# memory.net
KiCad netlist of a schematic drawn in Altium Designer
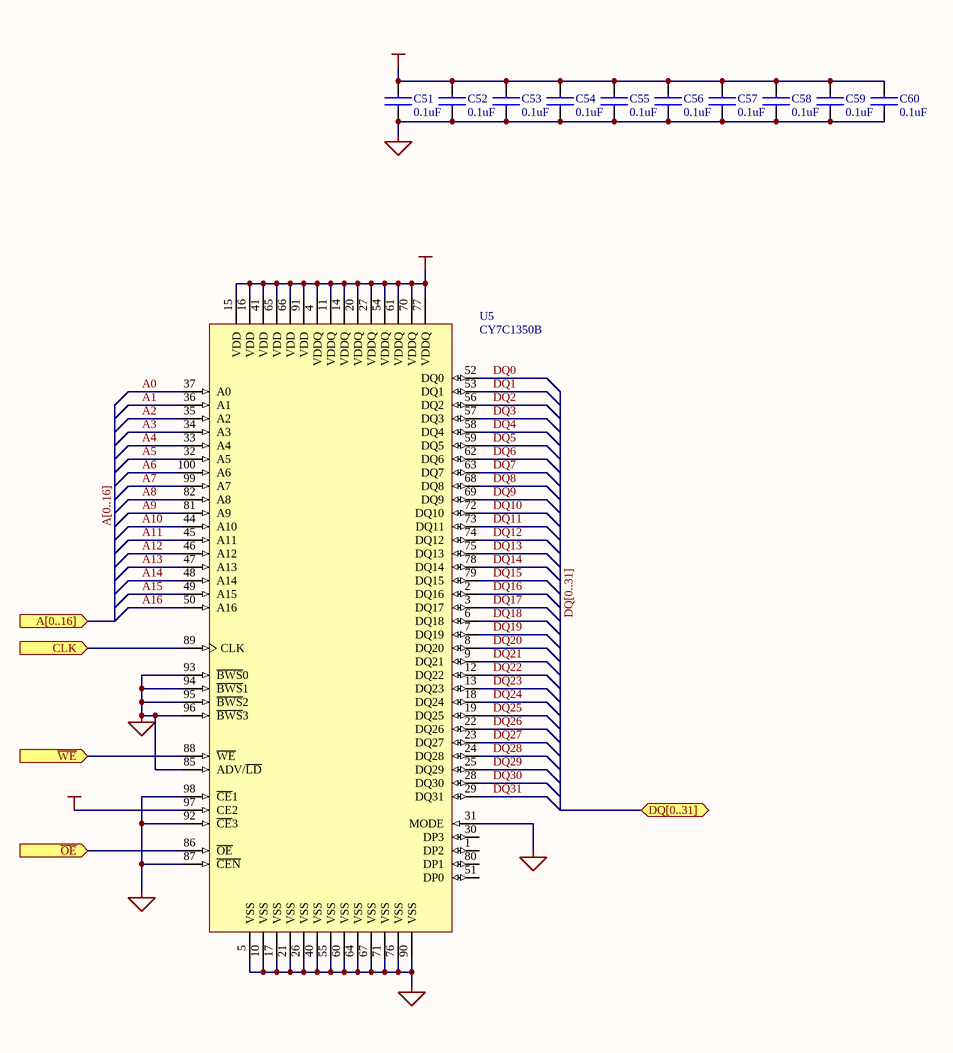
[diagram p0: memory.SCHDOC]

(export (version "E")
  (design (tool "Eeschema 10.0.6"))
  (components
    (comp (ref "C51")
      (value "0.1uF")
      (footprint "0603")
      (description "Standard Capacitor")
      (fields (field (name "Comment") "CAPACITOR"))
      (libsource (lib "parts") (part "CAPACITOR"))
    )
    (comp (ref "C52")
      (value "0.1uF")
      (footprint "0603")
      (description "Standard Capacitor")
      (fields (field (name "Comment") "CAPACITOR"))
      (libsource (lib "parts") (part "CAPACITOR"))
    )
    (comp (ref "C53")
      (value "0.1uF")
      (footprint "0603")
      (description "Standard Capacitor")
      (fields (field (name "Comment") "CAPACITOR"))
      (libsource (lib "parts") (part "CAPACITOR"))
    )
    (comp (ref "C54")
      (value "0.1uF")
      (footprint "0603")
      (description "Standard Capacitor")
      (fields (field (name "Comment") "CAPACITOR"))
      (libsource (lib "parts") (part "CAPACITOR"))
    )
    (comp (ref "C55")
      (value "0.1uF")
      (footprint "0603")
      (description "Standard Capacitor")
      (fields (field (name "Comment") "CAPACITOR"))
      (libsource (lib "parts") (part "CAPACITOR"))
    )
    (comp (ref "C56")
      (value "0.1uF")
      (footprint "0603")
      (description "Standard Capacitor")
      (fields (field (name "Comment") "CAPACITOR"))
      (libsource (lib "parts") (part "CAPACITOR"))
    )
    (comp (ref "C57")
      (value "0.1uF")
      (footprint "0603")
      (description "Standard Capacitor")
      (fields (field (name "Comment") "CAPACITOR"))
      (libsource (lib "parts") (part "CAPACITOR"))
    )
    (comp (ref "C58")
      (value "0.1uF")
      (footprint "0603")
      (description "Standard Capacitor")
      (fields (field (name "Comment") "CAPACITOR"))
      (libsource (lib "parts") (part "CAPACITOR"))
    )
    (comp (ref "C59")
      (value "0.1uF")
      (footprint "0603")
      (description "Standard Capacitor")
      (fields (field (name "Comment") "CAPACITOR"))
      (libsource (lib "parts") (part "CAPACITOR"))
    )
    (comp (ref "C60")
      (value "0.1uF")
      (footprint "0603")
      (description "Standard Capacitor")
      (fields (field (name "Comment") "CAPACITOR"))
      (libsource (lib "parts") (part "CAPACITOR"))
    )
    (comp (ref "U5")
      (value "CY7C1350B")
      (footprint "R-QFP14x20-G100/N")
      (description "Cypress NoBL Pipelined SRAM 128kx36")
      (libsource (lib "My devices") (part "CY7C1350B"))
    )
  )
  (nets
    (net (code "1") (name "/A0") (class "Default")
      (node (ref "U5") (pin "37") (pinfunction "A0_37") (pintype "input"))
    )
    (net (code "2") (name "/A1") (class "Default")
      (node (ref "U5") (pin "36") (pinfunction "A1_36") (pintype "input"))
    )
    (net (code "3") (name "/A2") (class "Default")
      (node (ref "U5") (pin "35") (pinfunction "A2_35") (pintype "input"))
    )
    (net (code "4") (name "/A3") (class "Default")
      (node (ref "U5") (pin "34") (pinfunction "A3_34") (pintype "input"))
    )
    (net (code "5") (name "/A4") (class "Default")
      (node (ref "U5") (pin "33") (pinfunction "A4_33") (pintype "input"))
    )
    (net (code "6") (name "/A5") (class "Default")
      (node (ref "U5") (pin "32") (pinfunction "A5_32") (pintype "input"))
    )
    (net (code "7") (name "/A6") (class "Default")
      (node (ref "U5") (pin "100") (pinfunction "A6_100") (pintype "input"))
    )
    (net (code "8") (name "/A7") (class "Default")
      (node (ref "U5") (pin "99") (pinfunction "A7_99") (pintype "input"))
    )
    (net (code "9") (name "/A8") (class "Default")
      (node (ref "U5") (pin "82") (pinfunction "A8_82") (pintype "input"))
    )
    (net (code "10") (name "/A9") (class "Default")
      (node (ref "U5") (pin "81") (pinfunction "A9_81") (pintype "input"))
    )
    (net (code "11") (name "/A10") (class "Default")
      (node (ref "U5") (pin "44") (pinfunction "A10_44") (pintype "input"))
    )
    (net (code "12") (name "/A11") (class "Default")
      (node (ref "U5") (pin "45") (pinfunction "A11_45") (pintype "input"))
    )
    (net (code "13") (name "/A12") (class "Default")
      (node (ref "U5") (pin "46") (pinfunction "A12_46") (pintype "input"))
    )
    (net (code "14") (name "/A13") (class "Default")
      (node (ref "U5") (pin "47") (pinfunction "A13_47") (pintype "input"))
    )
    (net (code "15") (name "/A14") (class "Default")
      (node (ref "U5") (pin "48") (pinfunction "A14_48") (pintype "input"))
    )
    (net (code "16") (name "/A15") (class "Default")
      (node (ref "U5") (pin "49") (pinfunction "A15_49") (pintype "input"))
    )
    (net (code "17") (name "/A16") (class "Default")
      (node (ref "U5") (pin "50") (pinfunction "A16_50") (pintype "input"))
    )
    (net (code "19") (name "/CLK") (class "Default")
      (node (ref "U5") (pin "89") (pinfunction "CLK_89") (pintype "input"))
    )
    (net (code "20") (name "/DQ0") (class "Default")
      (node (ref "U5") (pin "52") (pinfunction "DQ0_52") (pintype "bidirectional"))
    )
    (net (code "21") (name "/DQ1") (class "Default")
      (node (ref "U5") (pin "53") (pinfunction "DQ1_53") (pintype "bidirectional"))
    )
    (net (code "22") (name "/DQ2") (class "Default")
      (node (ref "U5") (pin "56") (pinfunction "DQ2_56") (pintype "bidirectional"))
    )
    (net (code "23") (name "/DQ3") (class "Default")
      (node (ref "U5") (pin "57") (pinfunction "DQ3_57") (pintype "bidirectional"))
    )
    (net (code "24") (name "/DQ4") (class "Default")
      (node (ref "U5") (pin "58") (pinfunction "DQ4_58") (pintype "bidirectional"))
    )
    (net (code "25") (name "/DQ5") (class "Default")
      (node (ref "U5") (pin "59") (pinfunction "DQ5_59") (pintype "bidirectional"))
    )
    (net (code "26") (name "/DQ6") (class "Default")
      (node (ref "U5") (pin "62") (pinfunction "DQ6_62") (pintype "bidirectional"))
    )
    (net (code "27") (name "/DQ7") (class "Default")
      (node (ref "U5") (pin "63") (pinfunction "DQ7_63") (pintype "bidirectional"))
    )
    (net (code "28") (name "/DQ8") (class "Default")
      (node (ref "U5") (pin "68") (pinfunction "DQ8_68") (pintype "bidirectional"))
    )
    (net (code "29") (name "/DQ9") (class "Default")
      (node (ref "U5") (pin "69") (pinfunction "DQ9_69") (pintype "bidirectional"))
    )
    (net (code "30") (name "/DQ10") (class "Default")
      (node (ref "U5") (pin "72") (pinfunction "DQ10_72") (pintype "bidirectional"))
    )
    (net (code "31") (name "/DQ11") (class "Default")
      (node (ref "U5") (pin "73") (pinfunction "DQ11_73") (pintype "bidirectional"))
    )
    (net (code "32") (name "/DQ12") (class "Default")
      (node (ref "U5") (pin "74") (pinfunction "DQ12_74") (pintype "bidirectional"))
    )
    (net (code "33") (name "/DQ13") (class "Default")
      (node (ref "U5") (pin "75") (pinfunction "DQ13_75") (pintype "bidirectional"))
    )
    (net (code "34") (name "/DQ14") (class "Default")
      (node (ref "U5") (pin "78") (pinfunction "DQ14_78") (pintype "bidirectional"))
    )
    (net (code "35") (name "/DQ15") (class "Default")
      (node (ref "U5") (pin "79") (pinfunction "DQ15_79") (pintype "bidirectional"))
    )
    (net (code "36") (name "/DQ16") (class "Default")
      (node (ref "U5") (pin "2") (pinfunction "DQ16_2") (pintype "bidirectional"))
    )
    (net (code "37") (name "/DQ17") (class "Default")
      (node (ref "U5") (pin "3") (pinfunction "DQ17_3") (pintype "bidirectional"))
    )
    (net (code "38") (name "/DQ18") (class "Default")
      (node (ref "U5") (pin "6") (pinfunction "DQ18_6") (pintype "bidirectional"))
    )
    (net (code "39") (name "/DQ19") (class "Default")
      (node (ref "U5") (pin "7") (pinfunction "DQ19_7") (pintype "bidirectional"))
    )
    (net (code "40") (name "/DQ20") (class "Default")
      (node (ref "U5") (pin "8") (pinfunction "DQ20_8") (pintype "bidirectional"))
    )
    (net (code "41") (name "/DQ21") (class "Default")
      (node (ref "U5") (pin "9") (pinfunction "DQ21_9") (pintype "bidirectional"))
    )
    (net (code "42") (name "/DQ22") (class "Default")
      (node (ref "U5") (pin "12") (pinfunction "DQ22_12") (pintype "bidirectional"))
    )
    (net (code "43") (name "/DQ23") (class "Default")
      (node (ref "U5") (pin "13") (pinfunction "DQ23_13") (pintype "bidirectional"))
    )
    (net (code "44") (name "/DQ24") (class "Default")
      (node (ref "U5") (pin "18") (pinfunction "DQ24_18") (pintype "bidirectional"))
    )
    (net (code "45") (name "/DQ25") (class "Default")
      (node (ref "U5") (pin "19") (pinfunction "DQ25_19") (pintype "bidirectional"))
    )
    (net (code "46") (name "/DQ26") (class "Default")
      (node (ref "U5") (pin "22") (pinfunction "DQ26_22") (pintype "bidirectional"))
    )
    (net (code "47") (name "/DQ27") (class "Default")
      (node (ref "U5") (pin "23") (pinfunction "DQ27_23") (pintype "bidirectional"))
    )
    (net (code "48") (name "/DQ28") (class "Default")
      (node (ref "U5") (pin "24") (pinfunction "DQ28_24") (pintype "bidirectional"))
    )
    (net (code "49") (name "/DQ29") (class "Default")
      (node (ref "U5") (pin "25") (pinfunction "DQ29_25") (pintype "bidirectional"))
    )
    (net (code "50") (name "/DQ30") (class "Default")
      (node (ref "U5") (pin "28") (pinfunction "DQ30_28") (pintype "bidirectional"))
    )
    (net (code "51") (name "/DQ31") (class "Default")
      (node (ref "U5") (pin "29") (pinfunction "DQ31_29") (pintype "bidirectional"))
    )
    (net (code "53") (name "/~{OE}") (class "Default")
      (node (ref "U5") (pin "86") (pinfunction "~{OE}_86") (pintype "input"))
    )
    (net (code "54") (name "/~{WE}") (class "Default")
      (node (ref "U5") (pin "88") (pinfunction "~{WE}_88") (pintype "input"))
    )
    (net (code "55") (name "GND") (class "Default")
      (node (ref "C51") (pin "1") (pintype "passive"))
      (node (ref "C52") (pin "1") (pintype "passive"))
      (node (ref "C53") (pin "1") (pintype "passive"))
      (node (ref "C54") (pin "1") (pintype "passive"))
      (node (ref "C55") (pin "1") (pintype "passive"))
      (node (ref "C56") (pin "1") (pintype "passive"))
      (node (ref "C57") (pin "1") (pintype "passive"))
      (node (ref "C58") (pin "1") (pintype "passive"))
      (node (ref "C59") (pin "1") (pintype "passive"))
      (node (ref "C60") (pin "2") (pintype "passive"))
      (node (ref "U5") (pin "10") (pinfunction "VSS_10") (pintype "power_in"))
      (node (ref "U5") (pin "17") (pinfunction "VSS_17") (pintype "power_in"))
      (node (ref "U5") (pin "21") (pinfunction "VSS_21") (pintype "power_in"))
      (node (ref "U5") (pin "26") (pinfunction "VSS_26") (pintype "power_in"))
      (node (ref "U5") (pin "31") (pinfunction "MODE_31") (pintype "input"))
      (node (ref "U5") (pin "40") (pinfunction "VSS_40") (pintype "power_in"))
      (node (ref "U5") (pin "5") (pinfunction "VSS_5") (pintype "power_in"))
      (node (ref "U5") (pin "55") (pinfunction "VSS_55") (pintype "power_in"))
      (node (ref "U5") (pin "60") (pinfunction "VSS_60") (pintype "power_in"))
      (node (ref "U5") (pin "64") (pinfunction "VSS_64") (pintype "power_in"))
      (node (ref "U5") (pin "67") (pinfunction "VSS_67") (pintype "power_in"))
      (node (ref "U5") (pin "71") (pinfunction "VSS_71") (pintype "power_in"))
      (node (ref "U5") (pin "76") (pinfunction "VSS_76") (pintype "power_in"))
      (node (ref "U5") (pin "85") (pinfunction "ADV/~{LD}_85") (pintype "input"))
      (node (ref "U5") (pin "87") (pinfunction "~{CEN}_87") (pintype "input"))
      (node (ref "U5") (pin "90") (pinfunction "VSS_90") (pintype "power_in"))
      (node (ref "U5") (pin "92") (pinfunction "~{CE}3_92") (pintype "input"))
      (node (ref "U5") (pin "93") (pinfunction "~{BWS}0_93") (pintype "input"))
      (node (ref "U5") (pin "94") (pinfunction "~{BWS}1_94") (pintype "input"))
      (node (ref "U5") (pin "95") (pinfunction "~{BWS}2_95") (pintype "input"))
      (node (ref "U5") (pin "96") (pinfunction "~{BWS}3_96") (pintype "input"))
      (node (ref "U5") (pin "98") (pinfunction "~{CE}1_98") (pintype "input"))
    )
    (net (code "56") (name "VCC") (class "Default")
      (node (ref "C51") (pin "2") (pintype "passive"))
      (node (ref "C52") (pin "2") (pintype "passive"))
      (node (ref "C53") (pin "2") (pintype "passive"))
      (node (ref "C54") (pin "2") (pintype "passive"))
      (node (ref "C55") (pin "2") (pintype "passive"))
      (node (ref "C56") (pin "2") (pintype "passive"))
      (node (ref "C57") (pin "2") (pintype "passive"))
      (node (ref "C58") (pin "2") (pintype "passive"))
      (node (ref "C59") (pin "2") (pintype "passive"))
      (node (ref "C60") (pin "1") (pintype "passive"))
      (node (ref "U5") (pin "11") (pinfunction "VDDQ_11") (pintype "power_in"))
      (node (ref "U5") (pin "14") (pinfunction "VDDQ_14") (pintype "power_in"))
      (node (ref "U5") (pin "15") (pinfunction "VDD_15") (pintype "power_in"))
      (node (ref "U5") (pin "16") (pinfunction "VDD_16") (pintype "power_in"))
      (node (ref "U5") (pin "20") (pinfunction "VDDQ_20") (pintype "power_in"))
      (node (ref "U5") (pin "27") (pinfunction "VDDQ_27") (pintype "power_in"))
      (node (ref "U5") (pin "4") (pinfunction "VDDQ_4") (pintype "power_in"))
      (node (ref "U5") (pin "41") (pinfunction "VDD_41") (pintype "power_in"))
      (node (ref "U5") (pin "54") (pinfunction "VDDQ_54") (pintype "power_in"))
      (node (ref "U5") (pin "61") (pinfunction "VDDQ_61") (pintype "power_in"))
      (node (ref "U5") (pin "65") (pinfunction "VDD_65") (pintype "power_in"))
      (node (ref "U5") (pin "66") (pinfunction "VDD_66") (pintype "power_in"))
      (node (ref "U5") (pin "70") (pinfunction "VDDQ_70") (pintype "power_in"))
      (node (ref "U5") (pin "77") (pinfunction "VDDQ_77") (pintype "power_in"))
      (node (ref "U5") (pin "91") (pinfunction "VDD_91") (pintype "power_in"))
      (node (ref "U5") (pin "97") (pinfunction "CE2_97") (pintype "input"))
    )
    (net (code "57") (name "unconnected-(U5-DP0-Pad51)") (class "Default")
      (node (ref "U5") (pin "51") (pinfunction "DP0_51") (pintype "bidirectional"))
    )
    (net (code "58") (name "unconnected-(U5-DP1-Pad80)") (class "Default")
      (node (ref "U5") (pin "80") (pinfunction "DP1_80") (pintype "bidirectional"))
    )
    (net (code "59") (name "unconnected-(U5-DP2-Pad1)") (class "Default")
      (node (ref "U5") (pin "1") (pinfunction "DP2_1") (pintype "bidirectional"))
    )
    (net (code "60") (name "unconnected-(U5-DP3-Pad30)") (class "Default")
      (node (ref "U5") (pin "30") (pinfunction "DP3_30") (pintype "bidirectional"))
    )
  )
)
